# tick-mini-mk-2_0.net
KiCad netlist of a schematic drawn in EAGLE
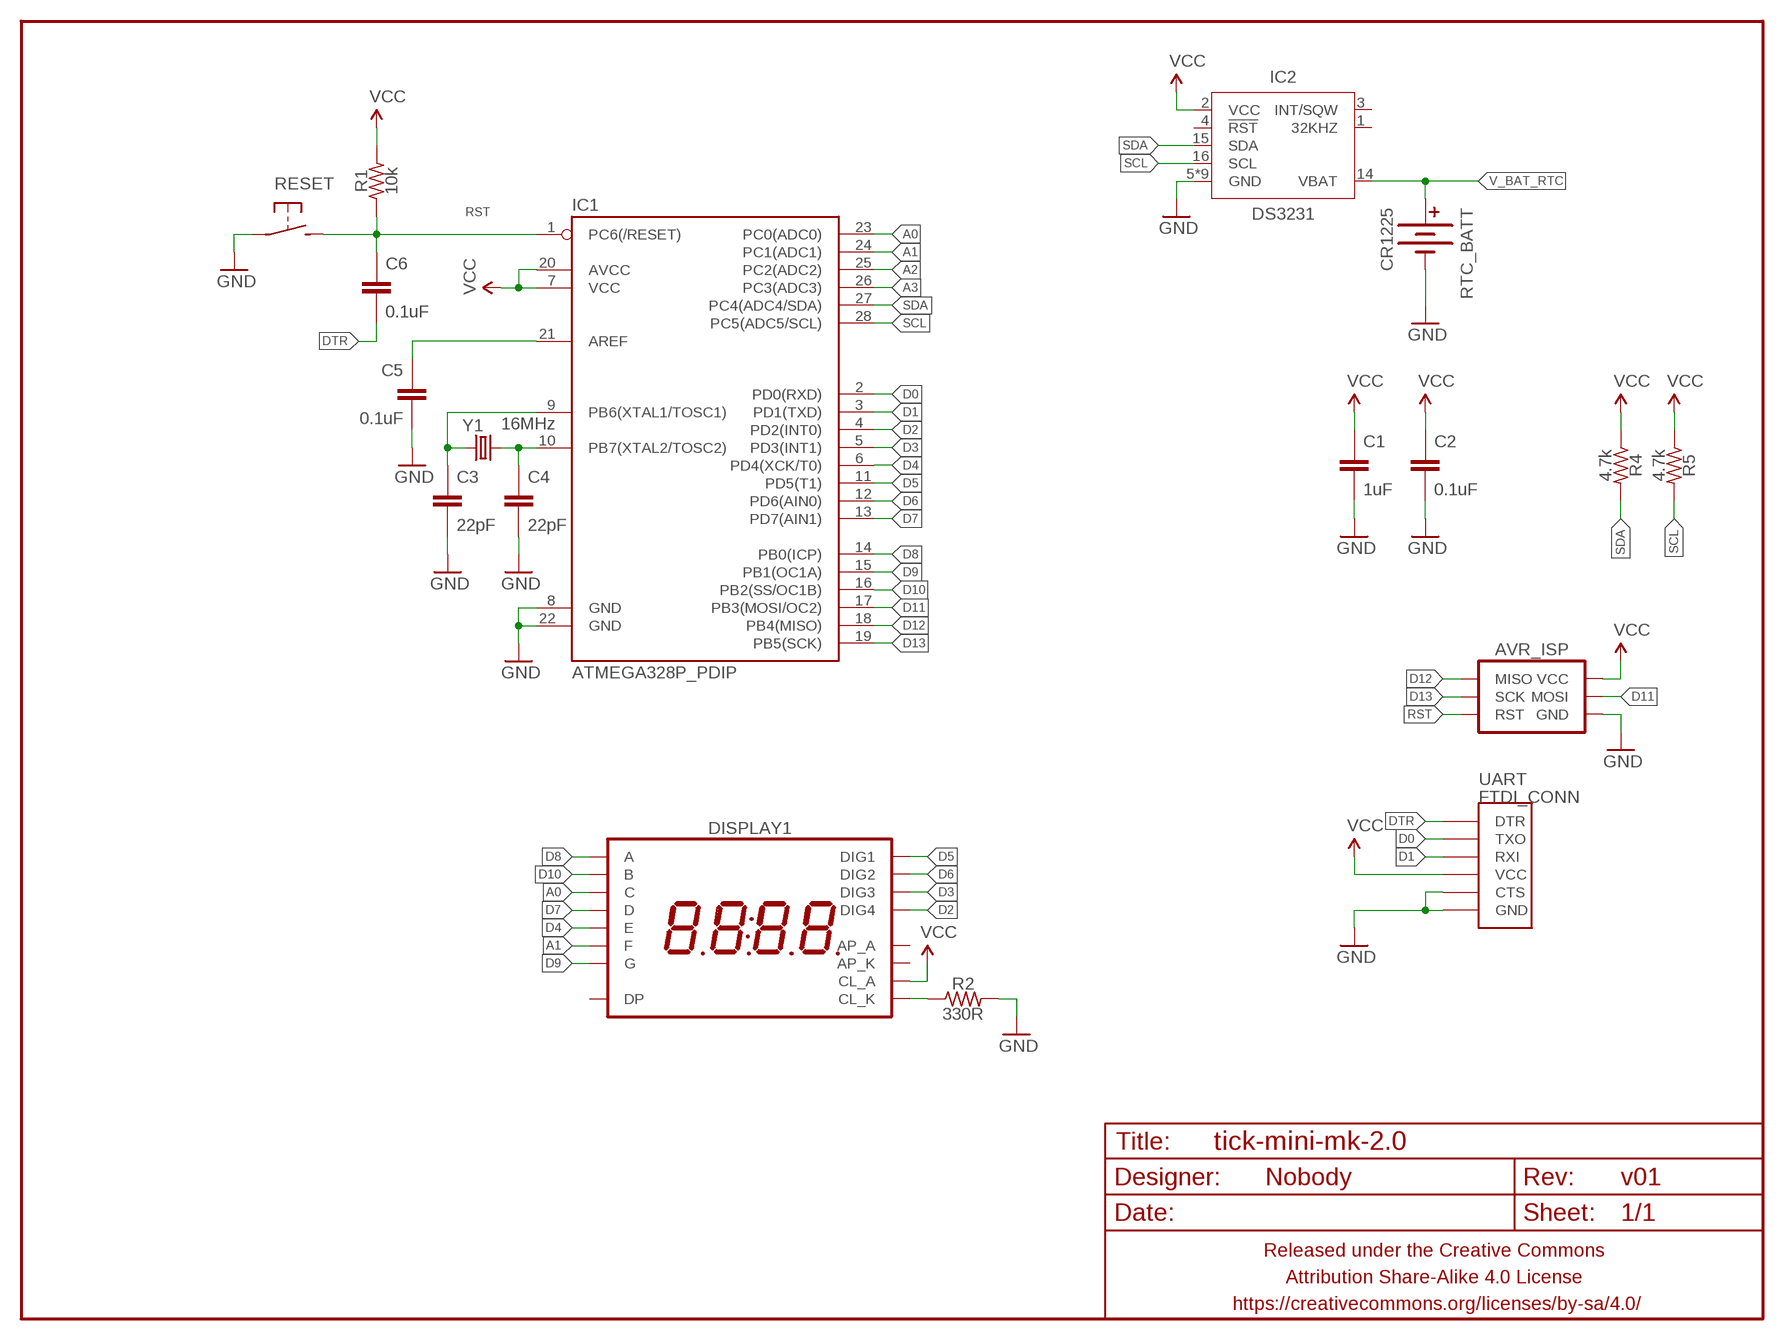
[diagram p0: schematic, sheet 1]

(export (version "E")
  (design (tool "Eeschema 10.0.6"))
  (components
    (comp (ref "AVR_ISP")
      (value "AVR_SPI_PRG_6PTH")
      (footprint "eagle-import:2X3")
      (libsource (lib "eagle-import") (part "AVR_SPI_PRG_6PTH"))
    )
    (comp (ref "C1")
      (value "1uF")
      (footprint "eagle-import:C025-024X044")
      (libsource (lib "eagle-import") (part "CAPACITOR-CERAMIC025-024X044"))
    )
    (comp (ref "C2")
      (value "0.1uF")
      (footprint "eagle-import:C025-024X044")
      (libsource (lib "eagle-import") (part "CAPACITOR-CERAMIC025-024X044"))
    )
    (comp (ref "C3")
      (value "22pF")
      (footprint "eagle-import:C025-024X044")
      (libsource (lib "eagle-import") (part "CAPACITOR-CERAMIC025-024X044"))
    )
    (comp (ref "C4")
      (value "22pF")
      (footprint "eagle-import:C025-024X044")
      (libsource (lib "eagle-import") (part "CAPACITOR-CERAMIC025-024X044"))
    )
    (comp (ref "C5")
      (value "0.1uF")
      (footprint "eagle-import:C025-024X044")
      (libsource (lib "eagle-import") (part "CAPACITOR-CERAMIC025-024X044"))
    )
    (comp (ref "C6")
      (value "0.1uF")
      (footprint "eagle-import:C025-024X044")
      (libsource (lib "eagle-import") (part "CAPACITOR-CERAMIC025-024X044"))
    )
    (comp (ref "DISPLAY1")
      (value "7SEG_4DIGIT_COLON_APOS")
      (footprint "eagle-import:7SEG_4DIG_10MM")
      (libsource (lib "eagle-import") (part "7SEG_4DIGIT_COLON_APOS"))
    )
    (comp (ref "FRAME1")
      (value "FRAME-LETTERNO_PACKAGE")
      (footprint "eagle-import:DUMMY")
      (fields (field (name "DESIGNER") "Nobody"))
      (libsource (lib "eagle-import") (part "FRAME-LETTERNO_PACKAGE"))
    )
    (comp (ref "IC1")
      (value "ATMEGA328P_PDIP")
      (footprint "eagle-import:DIL28-3")
      (libsource (lib "eagle-import") (part "ATMEGA328P_PDIP"))
    )
    (comp (ref "IC2")
      (value "DS3231")
      (footprint "eagle-import:SO16W")
      (libsource (lib "eagle-import") (part "DS3231"))
    )
    (comp (ref "R1")
      (value "10k")
      (footprint "eagle-import:RESISTOR-AXIAL-PTH-6.35MM")
      (libsource (lib "eagle-import") (part "RESISTORPTH-AXIAL-6.35MM"))
    )
    (comp (ref "R2")
      (value "330R")
      (footprint "eagle-import:RESISTOR-AXIAL-PTH-6.35MM")
      (libsource (lib "eagle-import") (part "RESISTORPTH-AXIAL-6.35MM"))
    )
    (comp (ref "R4")
      (value "4.7k")
      (footprint "eagle-import:RESISTOR-AXIAL-PTH-6.35MM")
      (libsource (lib "eagle-import") (part "RESISTORPTH-AXIAL-6.35MM"))
    )
    (comp (ref "R5")
      (value "4.7k")
      (footprint "eagle-import:RESISTOR-AXIAL-PTH-6.35MM")
      (libsource (lib "eagle-import") (part "RESISTORPTH-AXIAL-6.35MM"))
    )
    (comp (ref "RESET")
      (value "SPST-NO-TACT6MM-PTH-SMALL-PADS")
      (footprint "eagle-import:DTS-6-SMALL-PADS")
      (libsource (lib "eagle-import") (part "SPST-NO-TACT6MM-PTH-SMALL-PADS"))
    )
    (comp (ref "RTC_BATT")
      (value "CR1225")
      (footprint "eagle-import:BATTCON_12MM_PTH_TOPLOAD")
      (libsource (lib "eagle-import") (part "BATTERY12PTH_TOPLOAD"))
    )
    (comp (ref "UART")
      (value "FTDI_CONN")
      (footprint "eagle-import:FTDI_CONN")
      (libsource (lib "eagle-import") (part "FTDI_CONN"))
    )
    (comp (ref "Y1")
      (value "16MHz")
      (footprint "eagle-import:HC49U-V")
      (libsource (lib "eagle-import") (part "CRYSTALHC49UV"))
    )
  )
  (nets
    (net (code "1") (name "A0") (class "Default")
      (node (ref "DISPLAY1") (pin "13") (pinfunction "C_13") (pintype "passive"))
      (node (ref "IC1") (pin "23") (pinfunction "PC0(ADC0)_23") (pintype "bidirectional"))
    )
    (net (code "2") (name "A1") (class "Default")
      (node (ref "DISPLAY1") (pin "11") (pinfunction "F_11") (pintype "passive"))
      (node (ref "IC1") (pin "24") (pinfunction "PC1(ADC1)_24") (pintype "bidirectional"))
    )
    (net (code "3") (name "A2") (class "Default")
      (node (ref "IC1") (pin "25") (pinfunction "PC2(ADC2)_25") (pintype "bidirectional"))
    )
    (net (code "4") (name "A3") (class "Default")
      (node (ref "IC1") (pin "26") (pinfunction "PC3(ADC3)_26") (pintype "bidirectional"))
    )
    (net (code "5") (name "D0") (class "Default")
      (node (ref "IC1") (pin "2") (pinfunction "PD0(RXD)_2") (pintype "bidirectional"))
      (node (ref "UART") (pin "TXO") (pinfunction "TXO_TXO") (pintype "bidirectional"))
    )
    (net (code "6") (name "D1") (class "Default")
      (node (ref "IC1") (pin "3") (pinfunction "PD1(TXD)_3") (pintype "bidirectional"))
      (node (ref "UART") (pin "RXI") (pinfunction "RXI_RXI") (pintype "bidirectional"))
    )
    (net (code "7") (name "D2") (class "Default")
      (node (ref "DISPLAY1") (pin "8") (pinfunction "DIG4_8") (pintype "passive"))
      (node (ref "IC1") (pin "4") (pinfunction "PD2(INT0)_4") (pintype "bidirectional"))
    )
    (net (code "8") (name "D3") (class "Default")
      (node (ref "DISPLAY1") (pin "6") (pinfunction "DIG3_6") (pintype "passive"))
      (node (ref "IC1") (pin "5") (pinfunction "PD3(INT1)_5") (pintype "bidirectional"))
    )
    (net (code "9") (name "D4") (class "Default")
      (node (ref "DISPLAY1") (pin "5") (pinfunction "E_5") (pintype "passive"))
      (node (ref "IC1") (pin "6") (pinfunction "PD4(XCK/T0)_6") (pintype "bidirectional"))
    )
    (net (code "10") (name "D5") (class "Default")
      (node (ref "DISPLAY1") (pin "1") (pinfunction "DIG1_1") (pintype "passive"))
      (node (ref "IC1") (pin "11") (pinfunction "PD5(T1)_11") (pintype "bidirectional"))
    )
    (net (code "11") (name "D6") (class "Default")
      (node (ref "DISPLAY1") (pin "2") (pinfunction "DIG2_2") (pintype "passive"))
      (node (ref "IC1") (pin "12") (pinfunction "PD6(AIN0)_12") (pintype "bidirectional"))
    )
    (net (code "12") (name "D7") (class "Default")
      (node (ref "DISPLAY1") (pin "3") (pinfunction "D_3") (pintype "passive"))
      (node (ref "IC1") (pin "13") (pinfunction "PD7(AIN1)_13") (pintype "bidirectional"))
    )
    (net (code "13") (name "D8") (class "Default")
      (node (ref "DISPLAY1") (pin "14") (pinfunction "A_14") (pintype "passive"))
      (node (ref "IC1") (pin "14") (pinfunction "PB0(ICP)_14") (pintype "bidirectional"))
    )
    (net (code "14") (name "D9") (class "Default")
      (node (ref "DISPLAY1") (pin "15") (pinfunction "G_15") (pintype "passive"))
      (node (ref "IC1") (pin "15") (pinfunction "PB1(OC1A)_15") (pintype "bidirectional"))
    )
    (net (code "15") (name "D10") (class "Default")
      (node (ref "DISPLAY1") (pin "16") (pinfunction "B_16") (pintype "passive"))
      (node (ref "IC1") (pin "16") (pinfunction "PB2(SS/OC1B)_16") (pintype "bidirectional"))
    )
    (net (code "16") (name "D11") (class "Default")
      (node (ref "AVR_ISP") (pin "4") (pinfunction "MOSI_4") (pintype "passive"))
      (node (ref "IC1") (pin "17") (pinfunction "PB3(MOSI/OC2)_17") (pintype "bidirectional"))
    )
    (net (code "17") (name "D12") (class "Default")
      (node (ref "AVR_ISP") (pin "1") (pinfunction "MISO_1") (pintype "passive"))
      (node (ref "IC1") (pin "18") (pinfunction "PB4(MISO)_18") (pintype "bidirectional"))
    )
    (net (code "18") (name "D13") (class "Default")
      (node (ref "AVR_ISP") (pin "3") (pinfunction "SCK_3") (pintype "passive"))
      (node (ref "IC1") (pin "19") (pinfunction "PB5(SCK)_19") (pintype "bidirectional"))
    )
    (net (code "19") (name "DTR") (class "Default")
      (node (ref "C6") (pin "2") (pinfunction "2_2") (pintype "passive"))
      (node (ref "UART") (pin "DTR") (pinfunction "DTR_DTR") (pintype "bidirectional"))
    )
    (net (code "20") (name "GND") (class "Default")
      (node (ref "AVR_ISP") (pin "6") (pinfunction "GND_6") (pintype "passive"))
      (node (ref "C1") (pin "2") (pinfunction "2_2") (pintype "passive"))
      (node (ref "C2") (pin "2") (pinfunction "2_2") (pintype "passive"))
      (node (ref "C3") (pin "2") (pinfunction "2_2") (pintype "passive"))
      (node (ref "C4") (pin "2") (pinfunction "2_2") (pintype "passive"))
      (node (ref "C5") (pin "2") (pinfunction "2_2") (pintype "passive"))
      (node (ref "IC1") (pin "22") (pinfunction "GND_22") (pintype "bidirectional"))
      (node (ref "IC1") (pin "8") (pinfunction "GND_8") (pintype "bidirectional"))
      (node (ref "IC2") (pin "10") (pinfunction "GND_10") (pintype "bidirectional"))
      (node (ref "IC2") (pin "11") (pinfunction "GND_11") (pintype "bidirectional"))
      (node (ref "IC2") (pin "12") (pinfunction "GND_12") (pintype "bidirectional"))
      (node (ref "IC2") (pin "13") (pinfunction "GND_13") (pintype "bidirectional"))
      (node (ref "IC2") (pin "5") (pinfunction "GND_5") (pintype "bidirectional"))
      (node (ref "IC2") (pin "6") (pinfunction "GND_6") (pintype "bidirectional"))
      (node (ref "IC2") (pin "7") (pinfunction "GND_7") (pintype "bidirectional"))
      (node (ref "IC2") (pin "8") (pinfunction "GND_8") (pintype "bidirectional"))
      (node (ref "IC2") (pin "9") (pinfunction "GND_9") (pintype "bidirectional"))
      (node (ref "R2") (pin "P$2") (pinfunction "2_P$2") (pintype "passive"))
      (node (ref "RESET") (pin "1") (pinfunction "1_1") (pintype "passive"))
      (node (ref "RESET") (pin "2") (pinfunction "1_2") (pintype "passive"))
      (node (ref "RTC_BATT") (pin "-") (pinfunction "-_-") (pintype "power_in"))
      (node (ref "UART") (pin "CTS") (pinfunction "CTS_CTS") (pintype "bidirectional"))
      (node (ref "UART") (pin "GND") (pinfunction "GND_GND") (pintype "bidirectional"))
    )
    (net (code "21") (name "Net-(DISPLAY1-CL_K)") (class "Default")
      (node (ref "DISPLAY1") (pin "12") (pinfunction "CL_K_12") (pintype "passive"))
      (node (ref "R2") (pin "P$1") (pinfunction "1_P$1") (pintype "passive"))
    )
    (net (code "22") (name "Net-(IC1-AREF)") (class "Default")
      (node (ref "C5") (pin "1") (pinfunction "1_1") (pintype "passive"))
      (node (ref "IC1") (pin "21") (pinfunction "AREF_21") (pintype "bidirectional"))
    )
    (net (code "23") (name "Net-(IC1-PB6(XTAL1{slash}TOSC1))") (class "Default")
      (node (ref "C3") (pin "1") (pinfunction "1_1") (pintype "passive"))
      (node (ref "IC1") (pin "9") (pinfunction "PB6(XTAL1/TOSC1)_9") (pintype "bidirectional"))
      (node (ref "Y1") (pin "1") (pinfunction "1_1") (pintype "passive"))
    )
    (net (code "24") (name "Net-(IC1-PB7(XTAL2{slash}TOSC2))") (class "Default")
      (node (ref "C4") (pin "1") (pinfunction "1_1") (pintype "passive"))
      (node (ref "IC1") (pin "10") (pinfunction "PB7(XTAL2/TOSC2)_10") (pintype "bidirectional"))
      (node (ref "Y1") (pin "2") (pinfunction "2_2") (pintype "passive"))
    )
    (net (code "25") (name "RST") (class "Default")
      (node (ref "AVR_ISP") (pin "5") (pinfunction "RST_5") (pintype "passive"))
      (node (ref "C6") (pin "1") (pinfunction "1_1") (pintype "passive"))
      (node (ref "IC1") (pin "1") (pinfunction "PC6(/RESET)_1") (pintype "bidirectional"))
      (node (ref "R1") (pin "P$1") (pinfunction "1_P$1") (pintype "passive"))
      (node (ref "RESET") (pin "3") (pinfunction "2_3") (pintype "passive"))
      (node (ref "RESET") (pin "4") (pinfunction "2_4") (pintype "passive"))
    )
    (net (code "26") (name "SCL") (class "Default")
      (node (ref "IC1") (pin "28") (pinfunction "PC5(ADC5/SCL)_28") (pintype "bidirectional"))
      (node (ref "IC2") (pin "16") (pinfunction "SCL_16") (pintype "bidirectional"))
      (node (ref "R5") (pin "P$2") (pinfunction "2_P$2") (pintype "passive"))
    )
    (net (code "27") (name "SDA") (class "Default")
      (node (ref "IC1") (pin "27") (pinfunction "PC4(ADC4/SDA)_27") (pintype "bidirectional"))
      (node (ref "IC2") (pin "15") (pinfunction "SDA_15") (pintype "bidirectional"))
      (node (ref "R4") (pin "P$2") (pinfunction "2_P$2") (pintype "passive"))
    )
    (net (code "28") (name "VCC") (class "Default")
      (node (ref "AVR_ISP") (pin "2") (pinfunction "VCC_2") (pintype "passive"))
      (node (ref "C1") (pin "1") (pinfunction "1_1") (pintype "passive"))
      (node (ref "C2") (pin "1") (pinfunction "1_1") (pintype "passive"))
      (node (ref "DISPLAY1") (pin "4") (pinfunction "CL_A_4") (pintype "passive"))
      (node (ref "IC1") (pin "20") (pinfunction "AVCC_20") (pintype "bidirectional"))
      (node (ref "IC1") (pin "7") (pinfunction "VCC_7") (pintype "bidirectional"))
      (node (ref "IC2") (pin "2") (pinfunction "VCC_2") (pintype "bidirectional"))
      (node (ref "R1") (pin "P$2") (pinfunction "2_P$2") (pintype "passive"))
      (node (ref "R4") (pin "P$1") (pinfunction "1_P$1") (pintype "passive"))
      (node (ref "R5") (pin "P$1") (pinfunction "1_P$1") (pintype "passive"))
      (node (ref "UART") (pin "VCC") (pinfunction "VCC_VCC") (pintype "bidirectional"))
    )
    (net (code "29") (name "V_BAT_RTC") (class "Default")
      (node (ref "IC2") (pin "14") (pinfunction "VBAT_14") (pintype "bidirectional"))
      (node (ref "RTC_BATT") (pin "+") (pinfunction "+_+") (pintype "power_in"))
    )
    (net (code "30") (name "unconnected-(DISPLAY1-AP_A-Pad10)") (class "Default")
      (node (ref "DISPLAY1") (pin "10") (pinfunction "AP_A_10") (pintype "bidirectional"))
    )
    (net (code "31") (name "unconnected-(DISPLAY1-AP_K-Pad9)") (class "Default")
      (node (ref "DISPLAY1") (pin "9") (pinfunction "AP_K_9") (pintype "bidirectional"))
    )
    (net (code "32") (name "unconnected-(DISPLAY1-DP-Pad7)") (class "Default")
      (node (ref "DISPLAY1") (pin "7") (pinfunction "DP_7") (pintype "passive"))
    )
    (net (code "33") (name "unconnected-(IC2-32KHZ-Pad1)") (class "Default")
      (node (ref "IC2") (pin "1") (pinfunction "32KHZ_1") (pintype "bidirectional"))
    )
    (net (code "34") (name "unconnected-(IC2-INT{slash}SQW-Pad3)") (class "Default")
      (node (ref "IC2") (pin "3") (pinfunction "INT/SQW_3") (pintype "bidirectional"))
    )
    (net (code "35") (name "unconnected-(IC2-~{RST}-Pad4)") (class "Default")
      (node (ref "IC2") (pin "4") (pinfunction "~{RST}_4") (pintype "bidirectional"))
    )
  )
)
